# Schematic_1.net
KiCad netlist of a schematic drawn in Altium Designer
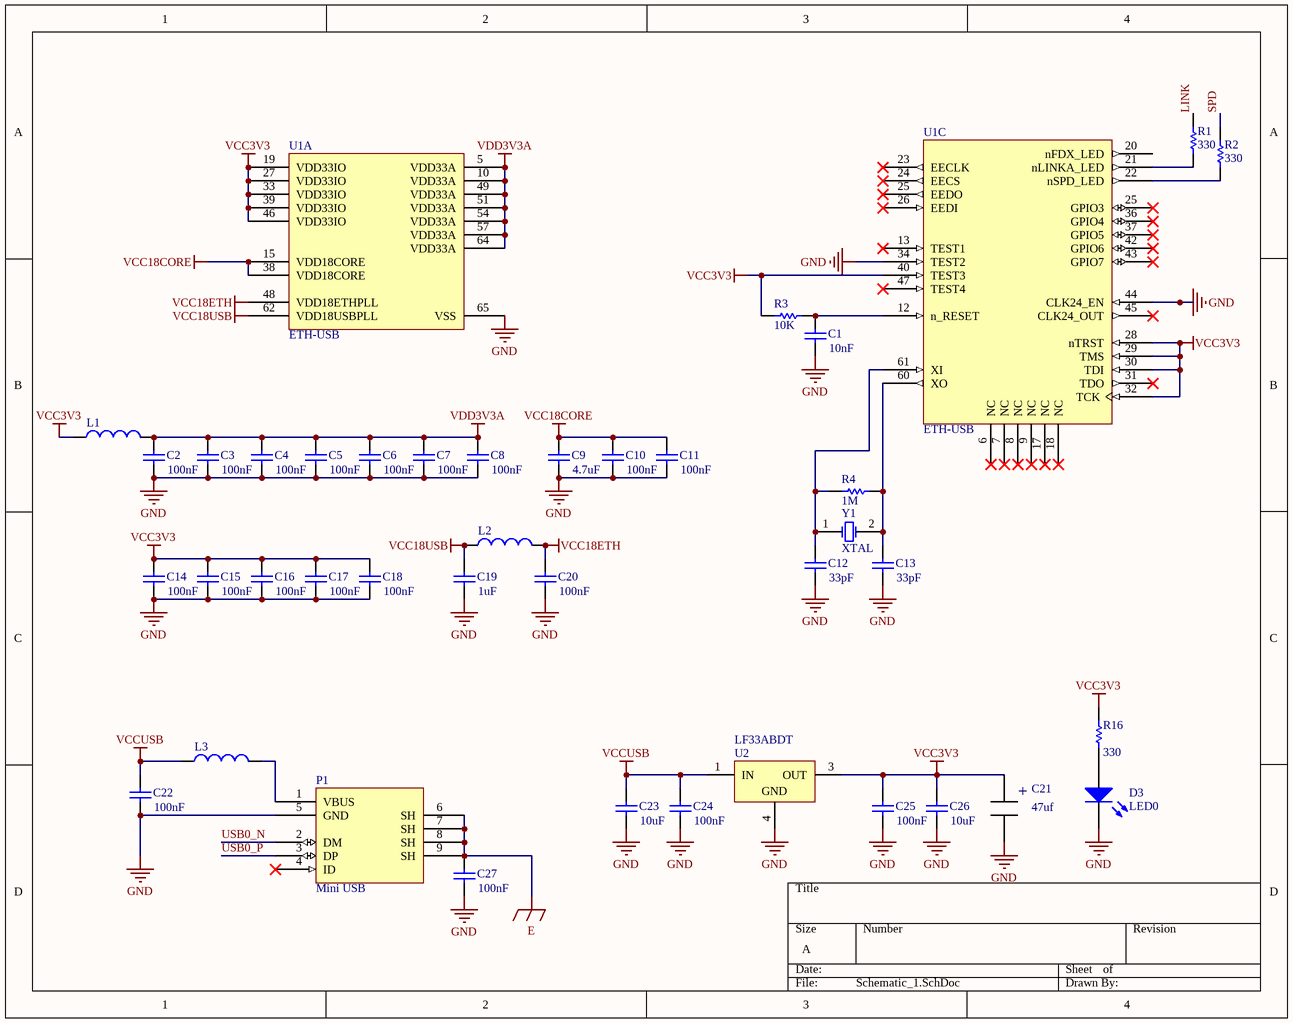
[diagram p0: Schematic_1.SchDoc]

(export (version "E")
  (design (tool "Eeschema 10.0.6"))
  (components
    (comp (ref "C1")
      (value "10nF")
      (footprint "C0805")
      (description "Capacitor")
      (fields (field (name "Comment") "Cap") (field (name "PUBLISHER") "Altium Limited"))
      (libsource (lib "Miscellaneous Devices") (part "Cap"))
    )
    (comp (ref "C2")
      (value "100nF")
      (footprint "C0805")
      (description "Capacitor")
      (fields (field (name "Comment") "Cap") (field (name "PUBLISHER") "Altium Limited"))
      (libsource (lib "Miscellaneous Devices") (part "Cap"))
    )
    (comp (ref "C3")
      (value "100nF")
      (footprint "C0805")
      (description "Capacitor")
      (fields (field (name "Comment") "Cap") (field (name "PUBLISHER") "Altium Limited"))
      (libsource (lib "Miscellaneous Devices") (part "Cap"))
    )
    (comp (ref "C4")
      (value "100nF")
      (footprint "C0805")
      (description "Capacitor")
      (fields (field (name "Comment") "Cap") (field (name "PUBLISHER") "Altium Limited"))
      (libsource (lib "Miscellaneous Devices") (part "Cap"))
    )
    (comp (ref "C5")
      (value "100nF")
      (footprint "C0805")
      (description "Capacitor")
      (fields (field (name "Comment") "Cap") (field (name "PUBLISHER") "Altium Limited"))
      (libsource (lib "Miscellaneous Devices") (part "Cap"))
    )
    (comp (ref "C6")
      (value "100nF")
      (footprint "C0805")
      (description "Capacitor")
      (fields (field (name "Comment") "Cap") (field (name "PUBLISHER") "Altium Limited"))
      (libsource (lib "Miscellaneous Devices") (part "Cap"))
    )
    (comp (ref "C7")
      (value "100nF")
      (footprint "C0805")
      (description "Capacitor")
      (fields (field (name "Comment") "Cap") (field (name "PUBLISHER") "Altium Limited"))
      (libsource (lib "Miscellaneous Devices") (part "Cap"))
    )
    (comp (ref "C8")
      (value "100nF")
      (footprint "C0805")
      (description "Capacitor")
      (fields (field (name "Comment") "Cap") (field (name "PUBLISHER") "Altium Limited"))
      (libsource (lib "Miscellaneous Devices") (part "Cap"))
    )
    (comp (ref "C9")
      (value "4.7uF")
      (footprint "C0805")
      (description "Capacitor")
      (fields (field (name "Comment") "Cap") (field (name "PUBLISHER") "Altium Limited"))
      (libsource (lib "Miscellaneous Devices") (part "Cap"))
    )
    (comp (ref "C10")
      (value "100nF")
      (footprint "C0805")
      (description "Capacitor")
      (fields (field (name "Comment") "Cap") (field (name "PUBLISHER") "Altium Limited"))
      (libsource (lib "Miscellaneous Devices") (part "Cap"))
    )
    (comp (ref "C11")
      (value "100nF")
      (footprint "C0805")
      (description "Capacitor")
      (fields (field (name "Comment") "Cap") (field (name "PUBLISHER") "Altium Limited"))
      (libsource (lib "Miscellaneous Devices") (part "Cap"))
    )
    (comp (ref "C12")
      (value "33pF")
      (footprint "C0805")
      (description "Capacitor")
      (fields (field (name "Comment") "Cap") (field (name "PUBLISHER") "Altium Limited"))
      (libsource (lib "Miscellaneous Devices") (part "Cap"))
    )
    (comp (ref "C13")
      (value "33pF")
      (footprint "C0805")
      (description "Capacitor")
      (fields (field (name "Comment") "Cap") (field (name "PUBLISHER") "Altium Limited"))
      (libsource (lib "Miscellaneous Devices") (part "Cap"))
    )
    (comp (ref "C14")
      (value "100nF")
      (footprint "C0805")
      (description "Capacitor")
      (fields (field (name "Comment") "Cap") (field (name "PUBLISHER") "Altium Limited"))
      (libsource (lib "Miscellaneous Devices") (part "Cap"))
    )
    (comp (ref "C15")
      (value "100nF")
      (footprint "C0805")
      (description "Capacitor")
      (fields (field (name "Comment") "Cap") (field (name "PUBLISHER") "Altium Limited"))
      (libsource (lib "Miscellaneous Devices") (part "Cap"))
    )
    (comp (ref "C16")
      (value "100nF")
      (footprint "C0805")
      (description "Capacitor")
      (fields (field (name "Comment") "Cap") (field (name "PUBLISHER") "Altium Limited"))
      (libsource (lib "Miscellaneous Devices") (part "Cap"))
    )
    (comp (ref "C17")
      (value "100nF")
      (footprint "C0805")
      (description "Capacitor")
      (fields (field (name "Comment") "Cap") (field (name "PUBLISHER") "Altium Limited"))
      (libsource (lib "Miscellaneous Devices") (part "Cap"))
    )
    (comp (ref "C18")
      (value "100nF")
      (footprint "C0805")
      (description "Capacitor")
      (fields (field (name "Comment") "Cap") (field (name "PUBLISHER") "Altium Limited"))
      (libsource (lib "Miscellaneous Devices") (part "Cap"))
    )
    (comp (ref "C19")
      (value "1uF")
      (footprint "C0805")
      (description "Capacitor")
      (fields (field (name "Comment") "Cap") (field (name "PUBLISHER") "Altium Limited"))
      (libsource (lib "Miscellaneous Devices") (part "Cap"))
    )
    (comp (ref "C20")
      (value "100nF")
      (footprint "C0805")
      (description "Capacitor")
      (fields (field (name "Comment") "Cap") (field (name "PUBLISHER") "Altium Limited"))
      (libsource (lib "Miscellaneous Devices") (part "Cap"))
    )
    (comp (ref "C21")
      (value "47uf")
      (footprint "Capacitor")
      (fields (field (name "Comment") "Capacitor"))
      (libsource (lib "Integrated_Library") (part "SMS capacitor"))
    )
    (comp (ref "C22")
      (value "100nF")
      (footprint "C0805")
      (description "Capacitor")
      (fields (field (name "Comment") "Cap") (field (name "PUBLISHER") "Altium Limited"))
      (libsource (lib "Miscellaneous Devices") (part "Cap"))
    )
    (comp (ref "C23")
      (value "10uF")
      (footprint "C0805")
      (description "Capacitor")
      (fields (field (name "Comment") "Cap") (field (name "PUBLISHER") "Altium Limited"))
      (libsource (lib "Miscellaneous Devices") (part "Cap"))
    )
    (comp (ref "C24")
      (value "100nF")
      (footprint "C0805")
      (description "Capacitor")
      (fields (field (name "Comment") "Cap") (field (name "PUBLISHER") "Altium Limited"))
      (libsource (lib "Miscellaneous Devices") (part "Cap"))
    )
    (comp (ref "C25")
      (value "100nF")
      (footprint "C0805")
      (description "Capacitor")
      (fields (field (name "Comment") "Cap") (field (name "PUBLISHER") "Altium Limited"))
      (libsource (lib "Miscellaneous Devices") (part "Cap"))
    )
    (comp (ref "C26")
      (value "10uF")
      (footprint "C0805")
      (description "Capacitor")
      (fields (field (name "Comment") "Cap") (field (name "PUBLISHER") "Altium Limited"))
      (libsource (lib "Miscellaneous Devices") (part "Cap"))
    )
    (comp (ref "C27")
      (value "100nF")
      (footprint "C0805")
      (description "Capacitor")
      (fields (field (name "Comment") "Cap") (field (name "PUBLISHER") "Altium Limited"))
      (libsource (lib "Miscellaneous Devices") (part "Cap"))
    )
    (comp (ref "D3")
      (value "LED0")
      (footprint "SMD_LED_1206")
      (description "Typical INFRARED GaAs LED")
      (fields (field (name "PUBLISHER") "Altium Limited"))
      (libsource (lib "Miscellaneous Devices") (part "LED0"))
    )
    (comp (ref "L1")
      (value "Inductor")
      (footprint "C1206")
      (fields (field (name "PUBLISHER") "Altium Limited"))
      (libsource (lib "Miscellaneous Devices") (part "Inductor"))
    )
    (comp (ref "L2")
      (value "Inductor")
      (footprint "C0805")
      (fields (field (name "PUBLISHER") "Altium Limited"))
      (libsource (lib "Miscellaneous Devices") (part "Inductor"))
    )
    (comp (ref "L3")
      (value "Inductor")
      (footprint "C1206")
      (fields (field (name "PUBLISHER") "Altium Limited"))
      (libsource (lib "Miscellaneous Devices") (part "Inductor"))
    )
    (comp (ref "P1")
      (value "Mini USB")
      (footprint "Mini USB")
      (libsource (lib "Conn_Schlib") (part "Mini USB"))
    )
    (comp (ref "R1")
      (value "330")
      (footprint "c0805")
      (description "Resistor")
      (fields (field (name "Comment") "Res1") (field (name "PUBLISHER") "Altium Limited"))
      (libsource (lib "Miscellaneous Devices") (part "Res1"))
    )
    (comp (ref "R2")
      (value "330")
      (footprint "c0805")
      (description "Resistor")
      (fields (field (name "Comment") "Res1") (field (name "PUBLISHER") "Altium Limited"))
      (libsource (lib "Miscellaneous Devices") (part "Res1"))
    )
    (comp (ref "R3")
      (value "10K")
      (footprint "c0805")
      (description "Resistor")
      (fields (field (name "Comment") "Res1") (field (name "PUBLISHER") "Altium Limited"))
      (libsource (lib "Miscellaneous Devices") (part "Res1"))
    )
    (comp (ref "R4")
      (value "1M")
      (footprint "c0805")
      (description "Resistor")
      (fields (field (name "Comment") "Res1") (field (name "PUBLISHER") "Altium Limited"))
      (libsource (lib "Miscellaneous Devices") (part "Res1"))
    )
    (comp (ref "R16")
      (value "330")
      (footprint "C1206")
      (description "Resistor")
      (fields (field (name "Comment") "Res1") (field (name "PUBLISHER") "Altium Limited"))
      (libsource (lib "Miscellaneous Devices") (part "Res1"))
    )
    (comp (ref "U1")
      (value "ETH-USB")
      (footprint "QFN64")
      (description "USB Hub to LAN connevtor")
      (libsource (lib "Connector_IntLib") (part "LAN9512"))
    )
    (comp (ref "U2")
      (value "LF33ABDT")
      (footprint "LF33-TO-252")
      (description "500mA, Very Low Drop (0.45V) Voltage Regulator")
      (fields (field (name "PUBLISHER") "Altium Limited"))
      (libsource (lib "ST Power Mgt Voltage Regulator") (part "LF33ABDT"))
    )
    (comp (ref "Y1")
      (value "XTAL")
      (footprint "SMD_Crystal")
      (description "Crystal Oscillator")
      (fields (field (name "PUBLISHER") "Altium Limited"))
      (libsource (lib "Miscellaneous Devices") (part "XTAL"))
    )
  )
  (nets
    (net (code "1") (name "/LINK") (class "Default")
      (node (ref "R1") (pin "1") (pinfunction "1_1") (pintype "passive"))
    )
    (net (code "2") (name "/SPD") (class "Default")
      (node (ref "R2") (pin "1") (pinfunction "1_1") (pintype "passive"))
    )
    (net (code "3") (name "/USB0_N") (class "Default")
      (node (ref "P1") (pin "2") (pinfunction "DM_2") (pintype "bidirectional"))
    )
    (net (code "4") (name "/USB0_P") (class "Default")
      (node (ref "P1") (pin "3") (pinfunction "DP_3") (pintype "bidirectional"))
    )
    (net (code "5") (name "E") (class "Default")
      (node (ref "C27") (pin "2") (pinfunction "2_2") (pintype "passive"))
      (node (ref "P1") (pin "6") (pinfunction "SH_6") (pintype "passive"))
      (node (ref "P1") (pin "7") (pinfunction "SH_7") (pintype "passive"))
      (node (ref "P1") (pin "8") (pinfunction "SH_8") (pintype "passive"))
      (node (ref "P1") (pin "9") (pinfunction "SH_9") (pintype "passive"))
    )
    (net (code "6") (name "GND") (class "Default")
      (node (ref "C1") (pin "1") (pinfunction "1_1") (pintype "passive"))
      (node (ref "C10") (pin "1") (pinfunction "1_1") (pintype "passive"))
      (node (ref "C11") (pin "1") (pinfunction "1_1") (pintype "passive"))
      (node (ref "C12") (pin "1") (pinfunction "1_1") (pintype "passive"))
      (node (ref "C13") (pin "1") (pinfunction "1_1") (pintype "passive"))
      (node (ref "C14") (pin "1") (pinfunction "1_1") (pintype "passive"))
      (node (ref "C15") (pin "1") (pinfunction "1_1") (pintype "passive"))
      (node (ref "C16") (pin "1") (pinfunction "1_1") (pintype "passive"))
      (node (ref "C17") (pin "1") (pinfunction "1_1") (pintype "passive"))
      (node (ref "C18") (pin "1") (pinfunction "1_1") (pintype "passive"))
      (node (ref "C19") (pin "1") (pinfunction "1_1") (pintype "passive"))
      (node (ref "C2") (pin "1") (pinfunction "1_1") (pintype "passive"))
      (node (ref "C20") (pin "1") (pinfunction "1_1") (pintype "passive"))
      (node (ref "C21") (pin "1") (pintype "power_in"))
      (node (ref "C22") (pin "1") (pinfunction "1_1") (pintype "passive"))
      (node (ref "C23") (pin "1") (pinfunction "1_1") (pintype "passive"))
      (node (ref "C24") (pin "1") (pinfunction "1_1") (pintype "passive"))
      (node (ref "C25") (pin "1") (pinfunction "1_1") (pintype "passive"))
      (node (ref "C26") (pin "1") (pinfunction "1_1") (pintype "passive"))
      (node (ref "C27") (pin "1") (pinfunction "1_1") (pintype "passive"))
      (node (ref "C3") (pin "1") (pinfunction "1_1") (pintype "passive"))
      (node (ref "C4") (pin "1") (pinfunction "1_1") (pintype "passive"))
      (node (ref "C5") (pin "1") (pinfunction "1_1") (pintype "passive"))
      (node (ref "C6") (pin "1") (pinfunction "1_1") (pintype "passive"))
      (node (ref "C7") (pin "1") (pinfunction "1_1") (pintype "passive"))
      (node (ref "C8") (pin "1") (pinfunction "1_1") (pintype "passive"))
      (node (ref "C9") (pin "1") (pinfunction "1_1") (pintype "passive"))
      (node (ref "D3") (pin "2") (pinfunction "K_2") (pintype "passive"))
      (node (ref "P1") (pin "5") (pinfunction "GND_5") (pintype "power_in"))
      (node (ref "U1") (pin "34") (pinfunction "TEST2_34") (pintype "input"))
      (node (ref "U1") (pin "44") (pinfunction "CLK24_EN_44") (pintype "input"))
      (node (ref "U1") (pin "65") (pinfunction "VSS_65") (pintype "power_in"))
      (node (ref "U2") (pin "4") (pinfunction "GND_4") (pintype "power_in"))
    )
    (net (code "7") (name "Net-(D3-A)") (class "Default")
      (node (ref "D3") (pin "1") (pinfunction "A_1") (pintype "passive"))
      (node (ref "R16") (pin "1") (pinfunction "1_1") (pintype "passive"))
    )
    (net (code "8") (name "Net-(P1-VBUS)") (class "Default")
      (node (ref "L3") (pin "2") (pinfunction "2_2") (pintype "passive"))
      (node (ref "P1") (pin "1") (pinfunction "VBUS_1") (pintype "power_in"))
    )
    (net (code "9") (name "Net-(U1C-XI)") (class "Default")
      (node (ref "C12") (pin "2") (pinfunction "2_2") (pintype "passive"))
      (node (ref "R4") (pin "2") (pinfunction "2_2") (pintype "passive"))
      (node (ref "U1") (pin "61") (pinfunction "XI_61") (pintype "input"))
      (node (ref "Y1") (pin "1") (pinfunction "OSC1_1") (pintype "passive"))
    )
    (net (code "10") (name "Net-(U1C-XO)") (class "Default")
      (node (ref "C13") (pin "2") (pinfunction "2_2") (pintype "passive"))
      (node (ref "R4") (pin "1") (pinfunction "1_1") (pintype "passive"))
      (node (ref "U1") (pin "60") (pinfunction "XO_60") (pintype "output"))
      (node (ref "Y1") (pin "2") (pinfunction "OSC2_2") (pintype "passive"))
    )
    (net (code "11") (name "Net-(U1C-nLINKA_LED)") (class "Default")
      (node (ref "R1") (pin "2") (pinfunction "2_2") (pintype "passive"))
      (node (ref "U1") (pin "21") (pinfunction "nLINKA_LED_21") (pintype "output"))
    )
    (net (code "12") (name "Net-(U1C-nSPD_LED)") (class "Default")
      (node (ref "R2") (pin "2") (pinfunction "2_2") (pintype "passive"))
      (node (ref "U1") (pin "22") (pinfunction "nSPD_LED_22") (pintype "output"))
    )
    (net (code "13") (name "Net-(U1C-n_RESET)") (class "Default")
      (node (ref "C1") (pin "2") (pinfunction "2_2") (pintype "passive"))
      (node (ref "R3") (pin "1") (pinfunction "1_1") (pintype "passive"))
      (node (ref "U1") (pin "12") (pinfunction "n_RESET_12") (pintype "input"))
    )
    (net (code "14") (name "VCC3V3") (class "Default")
      (node (ref "C14") (pin "2") (pinfunction "2_2") (pintype "passive"))
      (node (ref "C15") (pin "2") (pinfunction "2_2") (pintype "passive"))
      (node (ref "C16") (pin "2") (pinfunction "2_2") (pintype "passive"))
      (node (ref "C17") (pin "2") (pinfunction "2_2") (pintype "passive"))
      (node (ref "C18") (pin "2") (pinfunction "2_2") (pintype "passive"))
      (node (ref "C21") (pin "2") (pintype "power_in"))
      (node (ref "C25") (pin "2") (pinfunction "2_2") (pintype "passive"))
      (node (ref "C26") (pin "2") (pinfunction "2_2") (pintype "passive"))
      (node (ref "L1") (pin "1") (pinfunction "1_1") (pintype "passive"))
      (node (ref "R16") (pin "2") (pinfunction "2_2") (pintype "passive"))
      (node (ref "R3") (pin "2") (pinfunction "2_2") (pintype "passive"))
      (node (ref "U1") (pin "19") (pinfunction "VDD33IO_19") (pintype "power_in"))
      (node (ref "U1") (pin "27") (pinfunction "VDD33IO_27") (pintype "power_in"))
      (node (ref "U1") (pin "28") (pinfunction "nTRST_28") (pintype "input"))
      (node (ref "U1") (pin "29") (pinfunction "TMS_29") (pintype "input"))
      (node (ref "U1") (pin "30") (pinfunction "TDI_30") (pintype "input"))
      (node (ref "U1") (pin "32") (pinfunction "TCK_32") (pintype "input"))
      (node (ref "U1") (pin "33") (pinfunction "VDD33IO_33") (pintype "power_in"))
      (node (ref "U1") (pin "39") (pinfunction "VDD33IO_39") (pintype "power_in"))
      (node (ref "U1") (pin "40") (pinfunction "TEST3_40") (pintype "input"))
      (node (ref "U1") (pin "46") (pinfunction "VDD33IO_46") (pintype "power_in"))
      (node (ref "U2") (pin "3") (pinfunction "OUT_3") (pintype "power_in"))
    )
    (net (code "15") (name "VCC18CORE") (class "Default")
      (node (ref "C10") (pin "2") (pinfunction "2_2") (pintype "passive"))
      (node (ref "C11") (pin "2") (pinfunction "2_2") (pintype "passive"))
      (node (ref "C9") (pin "2") (pinfunction "2_2") (pintype "passive"))
      (node (ref "U1") (pin "15") (pinfunction "VDD18CORE_15") (pintype "power_in"))
      (node (ref "U1") (pin "38") (pinfunction "VDD18CORE_38") (pintype "power_in"))
    )
    (net (code "16") (name "VCC18ETH") (class "Default")
      (node (ref "C20") (pin "2") (pinfunction "2_2") (pintype "passive"))
      (node (ref "L2") (pin "2") (pinfunction "2_2") (pintype "passive"))
      (node (ref "U1") (pin "48") (pinfunction "VDD18ETHPLL_48") (pintype "power_in"))
    )
    (net (code "17") (name "VCC18USB") (class "Default")
      (node (ref "C19") (pin "2") (pinfunction "2_2") (pintype "passive"))
      (node (ref "L2") (pin "1") (pinfunction "1_1") (pintype "passive"))
      (node (ref "U1") (pin "62") (pinfunction "VDD18USBPLL_62") (pintype "power_in"))
    )
    (net (code "18") (name "VCCUSB") (class "Default")
      (node (ref "C22") (pin "2") (pinfunction "2_2") (pintype "passive"))
      (node (ref "C23") (pin "2") (pinfunction "2_2") (pintype "passive"))
      (node (ref "C24") (pin "2") (pinfunction "2_2") (pintype "passive"))
      (node (ref "L3") (pin "1") (pinfunction "1_1") (pintype "passive"))
      (node (ref "U2") (pin "1") (pinfunction "IN_1") (pintype "power_in"))
    )
    (net (code "19") (name "VDD3V3A") (class "Default")
      (node (ref "C2") (pin "2") (pinfunction "2_2") (pintype "passive"))
      (node (ref "C3") (pin "2") (pinfunction "2_2") (pintype "passive"))
      (node (ref "C4") (pin "2") (pinfunction "2_2") (pintype "passive"))
      (node (ref "C5") (pin "2") (pinfunction "2_2") (pintype "passive"))
      (node (ref "C6") (pin "2") (pinfunction "2_2") (pintype "passive"))
      (node (ref "C7") (pin "2") (pinfunction "2_2") (pintype "passive"))
      (node (ref "C8") (pin "2") (pinfunction "2_2") (pintype "passive"))
      (node (ref "L1") (pin "2") (pinfunction "2_2") (pintype "passive"))
      (node (ref "U1") (pin "10") (pinfunction "VDD33A_10") (pintype "power_in"))
      (node (ref "U1") (pin "49") (pinfunction "VDD33A_49") (pintype "power_in"))
      (node (ref "U1") (pin "5") (pinfunction "VDD33A_5") (pintype "power_in"))
      (node (ref "U1") (pin "51") (pinfunction "VDD33A_51") (pintype "power_in"))
      (node (ref "U1") (pin "54") (pinfunction "VDD33A_54") (pintype "power_in"))
      (node (ref "U1") (pin "57") (pinfunction "VDD33A_57") (pintype "power_in"))
      (node (ref "U1") (pin "64") (pinfunction "VDD33A_64") (pintype "power_in"))
    )
    (net (code "20") (name "unconnected-(P1-ID-Pad4)") (class "Default")
      (node (ref "P1") (pin "4") (pinfunction "ID_4") (pintype "input+no_connect"))
    )
    (net (code "21") (name "unconnected-(U1C-CLK24_OUT-Pad45)") (class "Default")
      (node (ref "U1") (pin "45") (pinfunction "CLK24_OUT_45") (pintype "output+no_connect"))
    )
    (net (code "22") (name "unconnected-(U1C-EECLK-Pad23)") (class "Default")
      (node (ref "U1") (pin "23") (pinfunction "EECLK_23") (pintype "output+no_connect"))
    )
    (net (code "23") (name "unconnected-(U1C-EECS-Pad24)") (class "Default")
      (node (ref "U1") (pin "24") (pinfunction "EECS_24") (pintype "output+no_connect"))
    )
    (net (code "24") (name "unconnected-(U1C-EEDI-Pad26)") (class "Default")
      (node (ref "U1") (pin "26") (pinfunction "EEDI_26") (pintype "input+no_connect"))
    )
    (net (code "25") (name "unconnected-(U1C-EEDO-Pad25)") (class "Default")
      (node (ref "U1") (pin "25") (pinfunction "EEDO_25") (pintype "output+no_connect"))
    )
    (net (code "26") (name "unconnected-(U1C-GPIO3-Pad25)") (class "Default")
      (node (ref "U1") (pin "25") (pinfunction "GPIO3_25") (pintype "bidirectional+no_connect"))
    )
    (net (code "27") (name "unconnected-(U1C-GPIO4-Pad36)") (class "Default")
      (node (ref "U1") (pin "36") (pinfunction "GPIO4_36") (pintype "bidirectional+no_connect"))
    )
    (net (code "28") (name "unconnected-(U1C-GPIO5-Pad37)") (class "Default")
      (node (ref "U1") (pin "37") (pinfunction "GPIO5_37") (pintype "bidirectional+no_connect"))
    )
    (net (code "29") (name "unconnected-(U1C-GPIO6-Pad42)") (class "Default")
      (node (ref "U1") (pin "42") (pinfunction "GPIO6_42") (pintype "bidirectional+no_connect"))
    )
    (net (code "30") (name "unconnected-(U1C-GPIO7-Pad43)") (class "Default")
      (node (ref "U1") (pin "43") (pinfunction "GPIO7_43") (pintype "bidirectional+no_connect"))
    )
    (net (code "31") (name "unconnected-(U1C-NC-Pad6)") (class "Default")
      (node (ref "U1") (pin "6") (pinfunction "NC_6") (pintype "passive+no_connect"))
    )
    (net (code "32") (name "unconnected-(U1C-NC-Pad7)") (class "Default")
      (node (ref "U1") (pin "7") (pinfunction "NC_7") (pintype "passive+no_connect"))
    )
    (net (code "33") (name "unconnected-(U1C-NC-Pad8)") (class "Default")
      (node (ref "U1") (pin "8") (pinfunction "NC_8") (pintype "passive+no_connect"))
    )
    (net (code "34") (name "unconnected-(U1C-NC-Pad9)") (class "Default")
      (node (ref "U1") (pin "9") (pinfunction "NC_9") (pintype "passive+no_connect"))
    )
    (net (code "35") (name "unconnected-(U1C-NC-Pad17)") (class "Default")
      (node (ref "U1") (pin "17") (pinfunction "NC_17") (pintype "passive+no_connect"))
    )
    (net (code "36") (name "unconnected-(U1C-NC-Pad18)") (class "Default")
      (node (ref "U1") (pin "18") (pinfunction "NC_18") (pintype "passive+no_connect"))
    )
    (net (code "37") (name "unconnected-(U1C-TDO-Pad31)") (class "Default")
      (node (ref "U1") (pin "31") (pinfunction "TDO_31") (pintype "output+no_connect"))
    )
    (net (code "38") (name "unconnected-(U1C-TEST1-Pad13)") (class "Default")
      (node (ref "U1") (pin "13") (pinfunction "TEST1_13") (pintype "input+no_connect"))
    )
    (net (code "39") (name "unconnected-(U1C-TEST4-Pad47)") (class "Default")
      (node (ref "U1") (pin "47") (pinfunction "TEST4_47") (pintype "input+no_connect"))
    )
    (net (code "40") (name "unconnected-(U1C-nFDX_LED-Pad20)") (class "Default")
      (node (ref "U1") (pin "20") (pinfunction "nFDX_LED_20") (pintype "output"))
    )
  )
)
